# SpinASM.net
KiCad netlist of a schematic drawn in Altium Designer
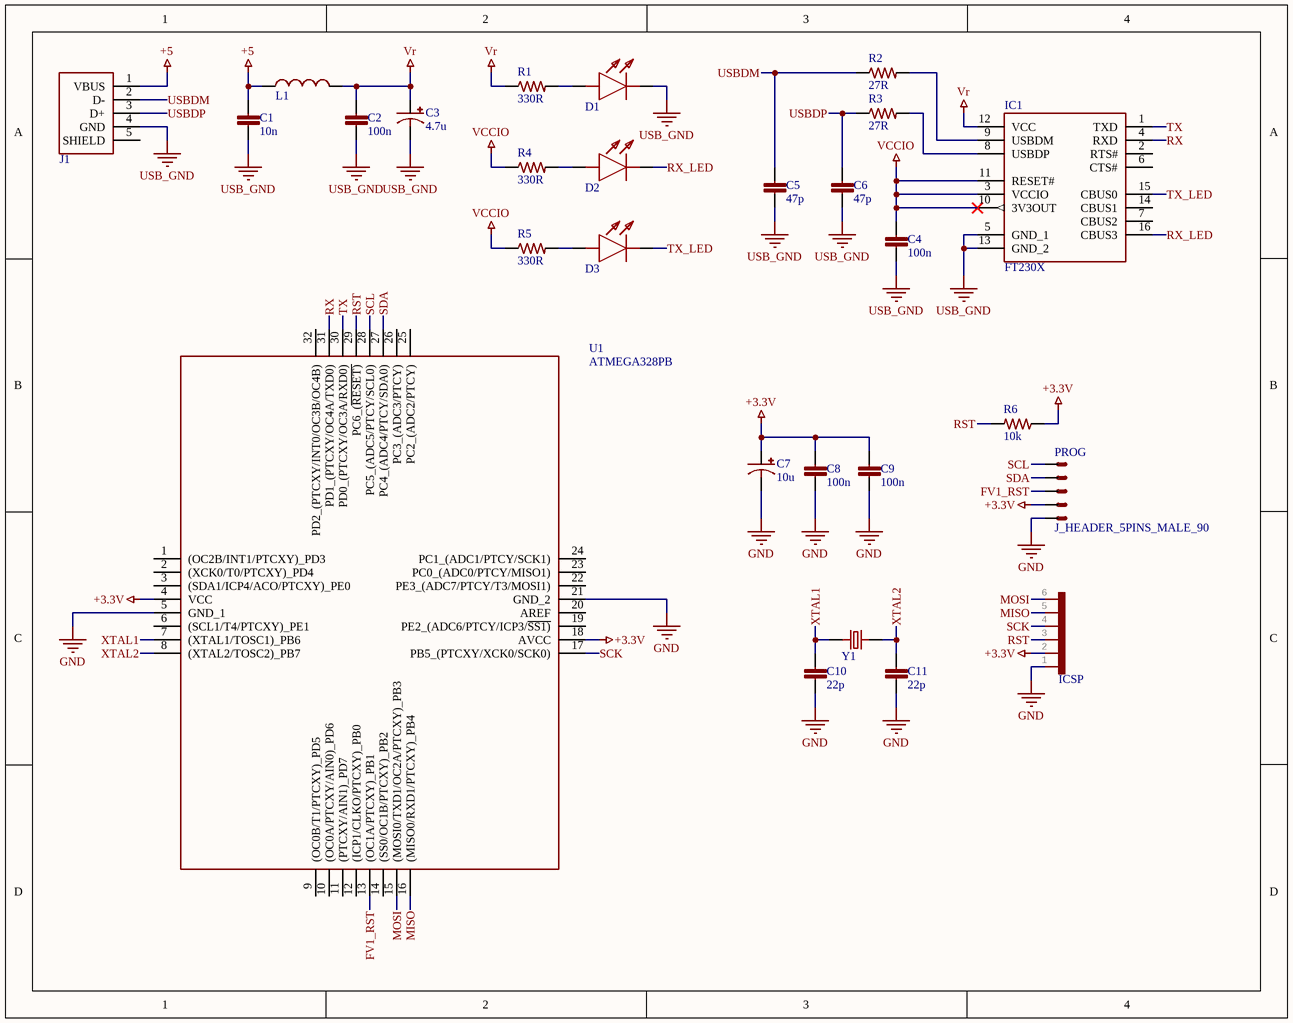
[diagram p0: SpinASM.SchDoc]

(export (version "E")
  (design (tool "Eeschema 10.0.6"))
  (components
    (comp (ref "C1")
      (value "10n")
      (footprint "CHIP_0603")
      (description "CAP CER 10NF 50V X7R 0603")
      (fields
        (field (name "MANUFACTURER") "Multicomp")
        (field (name "MANUFACTURER PART NUMBER") "MC0603B103K500CT")
      )
      (libsource (lib "Pedals SMD") (part "MC0603B103K500CT"))
    )
    (comp (ref "C2")
      (value "100n")
      (footprint "CHIP_0603")
      (description "CAP CER 100NF 50V X7R 0603")
      (fields
        (field (name "MANUFACTURER") "Multicomp")
        (field (name "MANUFACTURER PART NUMBER") "MC0603B104K500CT")
      )
      (libsource (lib "Pedals SMD") (part "MC0603B104K500CT"))
    )
    (comp (ref "C3")
      (value "4.7u")
      (footprint "TAN_1206")
      (description "CAP TANT 4.7UF 10V")
      (fields
        (field (name "MANUFACTURER") "KEMET")
        (field (name "MANUFACTURER PART NUMBER") "T491A475K010AT")
      )
      (libsource (lib "Pedals SMD") (part "T491A475K010AT"))
    )
    (comp (ref "C4")
      (value "100n")
      (footprint "CHIP_0603")
      (description "CAP CER 100NF 50V X7R 0603")
      (fields
        (field (name "MANUFACTURER") "Multicomp")
        (field (name "MANUFACTURER PART NUMBER") "MC0603B104K500CT")
      )
      (libsource (lib "Pedals SMD") (part "MC0603B104K500CT"))
    )
    (comp (ref "C5")
      (value "47p")
      (footprint "CHIP_0603")
      (description "CAP CER 47PF 50V C0G/NP0 0603")
      (fields
        (field (name "MANUFACTURER") "Multicomp")
        (field (name "MANUFACTURER PART NUMBER") "MC0603N470J500CT")
      )
      (libsource (lib "Pedals SMD") (part "MC0603N470J500CT"))
    )
    (comp (ref "C6")
      (value "47p")
      (footprint "CHIP_0603")
      (description "CAP CER 47PF 50V C0G/NP0 0603")
      (fields
        (field (name "MANUFACTURER") "Multicomp")
        (field (name "MANUFACTURER PART NUMBER") "MC0603N470J500CT")
      )
      (libsource (lib "Pedals SMD") (part "MC0603N470J500CT"))
    )
    (comp (ref "C7")
      (value "10u")
      (footprint "TAN_1206")
      (description "CAP TANT 10UF 16V")
      (fields
        (field (name "MANUFACTURER") "KEMET")
        (field (name "MANUFACTURER PART NUMBER") "T491A106K016AT")
      )
      (libsource (lib "Pedals SMD") (part "T491A106K016AT"))
    )
    (comp (ref "C8")
      (value "100n")
      (footprint "CHIP_0603")
      (description "CAP CER 100NF 50V X7R 0603")
      (fields
        (field (name "MANUFACTURER") "Multicomp")
        (field (name "MANUFACTURER PART NUMBER") "MC0603B104K500CT")
      )
      (libsource (lib "Pedals SMD") (part "MC0603B104K500CT"))
    )
    (comp (ref "C9")
      (value "100n")
      (footprint "CHIP_0603")
      (description "CAP CER 100NF 50V X7R 0603")
      (fields
        (field (name "MANUFACTURER") "Multicomp")
        (field (name "MANUFACTURER PART NUMBER") "MC0603B104K500CT")
      )
      (libsource (lib "Pedals SMD") (part "MC0603B104K500CT"))
    )
    (comp (ref "C10")
      (value "22p")
      (footprint "CHIP_0603")
      (description "CAP CER 22PF 50V C0G/NP0 0603")
      (fields
        (field (name "MANUFACTURER") "Multicomp")
        (field (name "MANUFACTURER PART NUMBER") "MC0603N220J500CT")
      )
      (libsource (lib "Pedals SMD") (part "MC0603N220J500CT"))
    )
    (comp (ref "C11")
      (value "22p")
      (footprint "CHIP_0603")
      (description "CAP CER 22PF 50V C0G/NP0 0603")
      (fields
        (field (name "MANUFACTURER") "Multicomp")
        (field (name "MANUFACTURER PART NUMBER") "MC0603N220J500CT")
      )
      (libsource (lib "Pedals SMD") (part "MC0603N220J500CT"))
    )
    (comp (ref "D1")
      (value "MP001249")
      (footprint "LED_0603")
      (description "LED RED CMS 603 20 mA 2.5 V 629 nm")
      (fields (field (name "MANUFACTURER") "Multicomp"))
      (libsource (lib "Pedals SMD") (part "MP001249"))
    )
    (comp (ref "D2")
      (value "MP001249")
      (footprint "LED_0603")
      (description "LED RED CMS 603 20 mA 2.5 V 629 nm")
      (fields (field (name "MANUFACTURER") "Multicomp"))
      (libsource (lib "Pedals SMD") (part "MP001249"))
    )
    (comp (ref "D3")
      (value "MP001249")
      (footprint "LED_0603")
      (description "LED RED CMS 603 20 mA 2.5 V 629 nm")
      (fields (field (name "MANUFACTURER") "Multicomp"))
      (libsource (lib "Pedals SMD") (part "MP001249"))
    )
    (comp (ref "IC1")
      (value "FT230X")
      (footprint "TSSOP-16")
      (description "USB-to-UART 1-CH 512byte FIFO 5V 16-Pin SSOP T/R")
      (fields (field (name "MANUFACTURER") "FTDI") (field (name "MANUFACTURER PART NUMBER") "FT230XS-R"))
      (libsource (lib "Pedals SMD") (part "FT230XS-R"))
    )
    (comp (ref "ICSP")
      (value "ICSP")
      (footprint "AVRISP_POGO")
      (libsource (lib "Pedals SMD") (part "AVRISP_POGO"))
    )
    (comp (ref "J1")
      (value "USB_MALE")
      (footprint "USB_MALE")
      (description "USB Connectors USB A PLUG SMT STR S SHELL LEG 3.8mm L/F")
      (fields (field (name "MANUFACTURER") "Molex") (field (name "MANUFACTURER PART NUMBER") "48037-2200"))
      (libsource (lib "Pedals SMD") (part "48037-2200"))
    )
    (comp (ref "L1")
      (value "BLM18AG331SN1D")
      (footprint "INDC1608X10")
      (description "MURATA         BLM18AG331SN1D            FERRITE BEAD, 0.3OHM, 500MA, 0603")
      (fields (field (name "MANUFACTURER") "Murata") (field (name "TOLERANCE") "25%"))
      (libsource (lib "Pedals SMD") (part "BLM18AG331SN1D"))
    )
    (comp (ref "PROG")
      (value "J_HEADER_5PINS_MALE_90")
      (footprint "HEADER_5PINS_MALE_90")
      (libsource (lib "Pedals") (part "J_HEADER_5PINS_MALE_90"))
    )
    (comp (ref "R1")
      (value "330R")
      (footprint "CHIP_R_0603")
      (description "RES SMD 330R OHM 1% 1/10W 0603")
      (fields
        (field (name "MANUFACTURER") "Vishay")
        (field (name "MANUFACTURER PART NUMBER") "CRCW0603330RFKEA")
      )
      (libsource (lib "Pedals SMD") (part "CRCW0603330RFKEA"))
    )
    (comp (ref "R2")
      (value "27R")
      (footprint "CHIP_R_0603")
      (description "RES SMD 27 OHM 1% 1/10W 0603")
      (fields
        (field (name "MANUFACTURER") "Vishay")
        (field (name "MANUFACTURER PART NUMBER") "CRCW060327R0FKEA")
      )
      (libsource (lib "Pedals SMD") (part "CRCW060327R0FKEA"))
    )
    (comp (ref "R3")
      (value "27R")
      (footprint "CHIP_R_0603")
      (description "RES SMD 27 OHM 1% 1/10W 0603")
      (fields
        (field (name "MANUFACTURER") "Vishay")
        (field (name "MANUFACTURER PART NUMBER") "CRCW060327R0FKEA")
      )
      (libsource (lib "Pedals SMD") (part "CRCW060327R0FKEA"))
    )
    (comp (ref "R4")
      (value "330R")
      (footprint "CHIP_R_0603")
      (description "RES SMD 330R OHM 1% 1/10W 0603")
      (fields
        (field (name "MANUFACTURER") "Vishay")
        (field (name "MANUFACTURER PART NUMBER") "CRCW0603330RFKEA")
      )
      (libsource (lib "Pedals SMD") (part "CRCW0603330RFKEA"))
    )
    (comp (ref "R5")
      (value "330R")
      (footprint "CHIP_R_0603")
      (description "RES SMD 330R OHM 1% 1/10W 0603")
      (fields
        (field (name "MANUFACTURER") "Vishay")
        (field (name "MANUFACTURER PART NUMBER") "CRCW0603330RFKEA")
      )
      (libsource (lib "Pedals SMD") (part "CRCW0603330RFKEA"))
    )
    (comp (ref "R6")
      (value "10k")
      (footprint "CHIP_R_0603")
      (description "RES SMD 10K OHM 1% 1/10W 0603")
      (fields
        (field (name "MANUFACTURER") "Vishay")
        (field (name "MANUFACTURER PART NUMBER") "CRCW060310K0FKEA")
      )
      (libsource (lib "Pedals SMD") (part "CRCW060310K0FKEA"))
    )
    (comp (ref "U1")
      (value "ATMEGA328PB")
      (footprint "TQFP32")
      (description "IC MCU 8BIT 32KB FLASH 32TQFP")
      (fields
        (field (name "MANUFACTURER") "Microchip")
        (field (name "MANUFACTURER PART NUMBER") "ATMEGA328PB-AU")
      )
      (libsource (lib "Pedals SMD") (part "ATMEGA328PB-AU"))
    )
    (comp (ref "Y1")
      (value "ABM10")
      (footprint "ABM10-167")
      (description "CRYSTAL 12 MHz SMD 28 pF 10 ppm")
      (fields
        (field (name "MANUFACTURER") "Abracon")
        (field (name "MANUFACTURER PART NUMBER") "ABM10-166-12.000MHZ-T3")
      )
      (libsource (lib "Pedals SMD") (part "ABM10-166-12.000MHZ-T3"))
    )
  )
  (nets
    (net (code "1") (name "+3.3V") (class "Default")
      (node (ref "C7") (pin "+") (pinfunction "+_+") (pintype "passive"))
      (node (ref "C8") (pin "1") (pinfunction "1_1") (pintype "passive"))
      (node (ref "C9") (pin "1") (pinfunction "1_1") (pintype "passive"))
      (node (ref "ICSP") (pin "2") (pinfunction "MOSI_2") (pintype "power_in"))
      (node (ref "PROG") (pin "2") (pinfunction "S_2") (pintype "passive"))
      (node (ref "R6") (pin "1") (pinfunction "1_1") (pintype "passive"))
      (node (ref "U1") (pin "18") (pinfunction "AVCC_18") (pintype "passive"))
      (node (ref "U1") (pin "4") (pinfunction "VCC_4") (pintype "passive"))
    )
    (net (code "2") (name "+5") (class "Default")
      (node (ref "C1") (pin "1") (pinfunction "1_1") (pintype "passive"))
      (node (ref "J1") (pin "1") (pinfunction "VBUS_1") (pintype "passive"))
      (node (ref "L1") (pin "2") (pinfunction "2_2") (pintype "passive"))
    )
    (net (code "3") (name "/FV1_RST") (class "Default")
      (node (ref "PROG") (pin "3") (pinfunction "S_3") (pintype "passive"))
      (node (ref "U1") (pin "13") (pinfunction "(OC1A/PTCXY)_PB1_13") (pintype "passive"))
    )
    (net (code "4") (name "/MISO") (class "Default")
      (node (ref "ICSP") (pin "5") (pinfunction "GND_5") (pintype "power_in"))
      (node (ref "U1") (pin "16") (pinfunction "(MISO0/RXD1/PTCXY)_PB4_16") (pintype "passive"))
    )
    (net (code "5") (name "/MOSI") (class "Default")
      (node (ref "ICSP") (pin "6") (pinfunction "VCC_6") (pintype "power_in"))
      (node (ref "U1") (pin "15") (pinfunction "(MOSI0/TXD1/OC2A/PTCXY)_PB3_15") (pintype "passive"))
    )
    (net (code "6") (name "/RST") (class "Default")
      (node (ref "ICSP") (pin "3") (pinfunction "MISO_3") (pintype "power_in"))
      (node (ref "R6") (pin "2") (pinfunction "2_2") (pintype "passive"))
      (node (ref "U1") (pin "29") (pinfunction "PC6_(~{RESET)}_29") (pintype "passive"))
    )
    (net (code "7") (name "/RX") (class "Default")
      (node (ref "IC1") (pin "4") (pinfunction "RXD_4") (pintype "passive"))
      (node (ref "U1") (pin "31") (pinfunction "PD1_(PTCXY/OC4A/TXD0)_31") (pintype "passive"))
    )
    (net (code "8") (name "/RX_LED") (class "Default")
      (node (ref "D2") (pin "1") (pinfunction "K_1") (pintype "passive"))
      (node (ref "IC1") (pin "16") (pinfunction "CBUS3_16") (pintype "passive"))
    )
    (net (code "9") (name "/SCK") (class "Default")
      (node (ref "ICSP") (pin "4") (pinfunction "SCK_4") (pintype "power_in"))
      (node (ref "U1") (pin "17") (pinfunction "PB5_(PTCXY/XCK0/SCK0)_17") (pintype "passive"))
    )
    (net (code "10") (name "/SCL") (class "Default")
      (node (ref "PROG") (pin "5") (pinfunction "S_5") (pintype "passive"))
      (node (ref "U1") (pin "28") (pinfunction "PC5_(ADC5/PTCY/SCL0)_28") (pintype "passive"))
    )
    (net (code "11") (name "/SDA") (class "Default")
      (node (ref "PROG") (pin "4") (pinfunction "S_4") (pintype "passive"))
      (node (ref "U1") (pin "27") (pinfunction "PC4_(ADC4/PTCY/SDA0)_27") (pintype "passive"))
    )
    (net (code "12") (name "/TX") (class "Default")
      (node (ref "IC1") (pin "1") (pinfunction "TXD_1") (pintype "passive"))
      (node (ref "U1") (pin "30") (pinfunction "PD0_(PTCXY/OC3A/RXD0)_30") (pintype "passive"))
    )
    (net (code "13") (name "/TX_LED") (class "Default")
      (node (ref "D3") (pin "1") (pinfunction "K_1") (pintype "passive"))
      (node (ref "IC1") (pin "15") (pinfunction "CBUS0_15") (pintype "passive"))
    )
    (net (code "14") (name "/USBDM") (class "Default")
      (node (ref "C5") (pin "1") (pinfunction "1_1") (pintype "passive"))
      (node (ref "J1") (pin "2") (pinfunction "D-_2") (pintype "passive"))
      (node (ref "R2") (pin "1") (pinfunction "1_1") (pintype "passive"))
    )
    (net (code "15") (name "/USBDP") (class "Default")
      (node (ref "C6") (pin "1") (pinfunction "1_1") (pintype "passive"))
      (node (ref "J1") (pin "3") (pinfunction "D+_3") (pintype "passive"))
      (node (ref "R3") (pin "1") (pinfunction "1_1") (pintype "passive"))
    )
    (net (code "16") (name "/XTAL1") (class "Default")
      (node (ref "C10") (pin "1") (pinfunction "1_1") (pintype "passive"))
      (node (ref "U1") (pin "7") (pinfunction "(XTAL1/TOSC1)_PB6_7") (pintype "passive"))
      (node (ref "Y1") (pin "1") (pinfunction "1_1") (pintype "passive"))
    )
    (net (code "17") (name "/XTAL2") (class "Default")
      (node (ref "C11") (pin "1") (pinfunction "1_1") (pintype "passive"))
      (node (ref "U1") (pin "8") (pinfunction "(XTAL2/TOSC2)_PB7_8") (pintype "passive"))
      (node (ref "Y1") (pin "2") (pinfunction "2_2") (pintype "passive"))
    )
    (net (code "18") (name "GND") (class "Default")
      (node (ref "C10") (pin "2") (pinfunction "2_2") (pintype "passive"))
      (node (ref "C11") (pin "2") (pinfunction "2_2") (pintype "passive"))
      (node (ref "C7") (pin "-") (pinfunction "-_-") (pintype "passive"))
      (node (ref "C8") (pin "2") (pinfunction "2_2") (pintype "passive"))
      (node (ref "C9") (pin "2") (pinfunction "2_2") (pintype "passive"))
      (node (ref "ICSP") (pin "1") (pinfunction "RST_1") (pintype "power_in"))
      (node (ref "PROG") (pin "1") (pinfunction "S_1") (pintype "passive"))
      (node (ref "U1") (pin "21") (pinfunction "GND_2_21") (pintype "passive"))
      (node (ref "U1") (pin "5") (pinfunction "GND_1_5") (pintype "passive"))
    )
    (net (code "19") (name "Net-(D1-A)") (class "Default")
      (node (ref "D1") (pin "2") (pinfunction "A_2") (pintype "passive"))
      (node (ref "R1") (pin "2") (pinfunction "2_2") (pintype "passive"))
    )
    (net (code "20") (name "Net-(D2-A)") (class "Default")
      (node (ref "D2") (pin "2") (pinfunction "A_2") (pintype "passive"))
      (node (ref "R4") (pin "2") (pinfunction "2_2") (pintype "passive"))
    )
    (net (code "21") (name "Net-(D3-A)") (class "Default")
      (node (ref "D3") (pin "2") (pinfunction "A_2") (pintype "passive"))
      (node (ref "R5") (pin "2") (pinfunction "2_2") (pintype "passive"))
    )
    (net (code "22") (name "Net-(IC1-USBDM)") (class "Default")
      (node (ref "IC1") (pin "9") (pinfunction "USBDM_9") (pintype "passive"))
      (node (ref "R2") (pin "2") (pinfunction "2_2") (pintype "passive"))
    )
    (net (code "23") (name "Net-(IC1-USBDP)") (class "Default")
      (node (ref "IC1") (pin "8") (pinfunction "USBDP_8") (pintype "passive"))
      (node (ref "R3") (pin "2") (pinfunction "2_2") (pintype "passive"))
    )
    (net (code "24") (name "USB_GND") (class "Default")
      (node (ref "C1") (pin "2") (pinfunction "2_2") (pintype "passive"))
      (node (ref "C2") (pin "2") (pinfunction "2_2") (pintype "passive"))
      (node (ref "C3") (pin "-") (pinfunction "-_-") (pintype "passive"))
      (node (ref "C4") (pin "2") (pinfunction "2_2") (pintype "passive"))
      (node (ref "C5") (pin "2") (pinfunction "2_2") (pintype "passive"))
      (node (ref "C6") (pin "2") (pinfunction "2_2") (pintype "passive"))
      (node (ref "D1") (pin "1") (pinfunction "K_1") (pintype "passive"))
      (node (ref "IC1") (pin "13") (pinfunction "GND_2_13") (pintype "power_in"))
      (node (ref "IC1") (pin "5") (pinfunction "GND_1_5") (pintype "power_in"))
      (node (ref "J1") (pin "4") (pinfunction "GND_4") (pintype "passive"))
    )
    (net (code "25") (name "VCCIO") (class "Default")
      (node (ref "C4") (pin "1") (pinfunction "1_1") (pintype "passive"))
      (node (ref "IC1") (pin "10") (pinfunction "3V3OUT_10") (pintype "output"))
      (node (ref "IC1") (pin "11") (pinfunction "RESET#_11") (pintype "passive"))
      (node (ref "IC1") (pin "3") (pinfunction "VCCIO_3") (pintype "power_in"))
      (node (ref "R4") (pin "1") (pinfunction "1_1") (pintype "passive"))
      (node (ref "R5") (pin "1") (pinfunction "1_1") (pintype "passive"))
    )
    (net (code "26") (name "Vr") (class "Default")
      (node (ref "C2") (pin "1") (pinfunction "1_1") (pintype "passive"))
      (node (ref "C3") (pin "+") (pinfunction "+_+") (pintype "passive"))
      (node (ref "IC1") (pin "12") (pinfunction "VCC_12") (pintype "power_in"))
      (node (ref "L1") (pin "1") (pinfunction "1_1") (pintype "passive"))
      (node (ref "R1") (pin "1") (pinfunction "1_1") (pintype "passive"))
    )
    (net (code "27") (name "unconnected-(IC1-CBUS1-Pad14)") (class "Default")
      (node (ref "IC1") (pin "14") (pinfunction "CBUS1_14") (pintype "passive"))
    )
    (net (code "28") (name "unconnected-(IC1-CBUS2-Pad7)") (class "Default")
      (node (ref "IC1") (pin "7") (pinfunction "CBUS2_7") (pintype "passive"))
    )
    (net (code "29") (name "unconnected-(IC1-CTS#-Pad6)") (class "Default")
      (node (ref "IC1") (pin "6") (pinfunction "CTS#_6") (pintype "passive"))
    )
    (net (code "30") (name "unconnected-(IC1-RTS#-Pad2)") (class "Default")
      (node (ref "IC1") (pin "2") (pinfunction "RTS#_2") (pintype "passive"))
    )
    (net (code "31") (name "unconnected-(J1-SHIELD-Pad5)") (class "Default")
      (node (ref "J1") (pin "5") (pinfunction "SHIELD_5") (pintype "passive"))
    )
    (net (code "32") (name "unconnected-(U1-(ICP1{slash}CLKO{slash}PTCXY)_PB0-Pad12)") (class "Default")
      (node (ref "U1") (pin "12") (pinfunction "(ICP1/CLKO/PTCXY)_PB0_12") (pintype "passive"))
    )
    (net (code "33") (name "unconnected-(U1-(OC0A{slash}PTCXY{slash}AIN0)_PD6-Pad10)") (class "Default")
      (node (ref "U1") (pin "10") (pinfunction "(OC0A/PTCXY/AIN0)_PD6_10") (pintype "passive"))
    )
    (net (code "34") (name "unconnected-(U1-(OC0B{slash}T1{slash}PTCXY)_PD5-Pad9)") (class "Default")
      (node (ref "U1") (pin "9") (pinfunction "(OC0B/T1/PTCXY)_PD5_9") (pintype "passive"))
    )
    (net (code "35") (name "unconnected-(U1-(OC2B{slash}INT1{slash}PTCXY)_PD3-Pad1)") (class "Default")
      (node (ref "U1") (pin "1") (pinfunction "(OC2B/INT1/PTCXY)_PD3_1") (pintype "passive"))
    )
    (net (code "36") (name "unconnected-(U1-(PTCXY{slash}AIN1)_PD7-Pad11)") (class "Default")
      (node (ref "U1") (pin "11") (pinfunction "(PTCXY/AIN1)_PD7_11") (pintype "passive"))
    )
    (net (code "37") (name "unconnected-(U1-(SCL1{slash}T4{slash}PTCXY)_PE1-Pad6)") (class "Default")
      (node (ref "U1") (pin "6") (pinfunction "(SCL1/T4/PTCXY)_PE1_6") (pintype "passive"))
    )
    (net (code "38") (name "unconnected-(U1-(SDA1{slash}ICP4{slash}ACO{slash}PTCXY)_PE0-Pad3)") (class "Default")
      (node (ref "U1") (pin "3") (pinfunction "(SDA1/ICP4/ACO/PTCXY)_PE0_3") (pintype "passive"))
    )
    (net (code "39") (name "unconnected-(U1-(SS0{slash}OC1B{slash}PTCXY)_PB2-Pad14)") (class "Default")
      (node (ref "U1") (pin "14") (pinfunction "(SS0/OC1B/PTCXY)_PB2_14") (pintype "passive"))
    )
    (net (code "40") (name "unconnected-(U1-(XCK0{slash}T0{slash}PTCXY)_PD4-Pad2)") (class "Default")
      (node (ref "U1") (pin "2") (pinfunction "(XCK0/T0/PTCXY)_PD4_2") (pintype "passive"))
    )
    (net (code "41") (name "unconnected-(U1-AREF-Pad20)") (class "Default")
      (node (ref "U1") (pin "20") (pinfunction "AREF_20") (pintype "passive"))
    )
    (net (code "42") (name "unconnected-(U1-PC0_(ADC0{slash}PTCY{slash}MISO1)-Pad23)") (class "Default")
      (node (ref "U1") (pin "23") (pinfunction "PC0_(ADC0/PTCY/MISO1)_23") (pintype "passive"))
    )
    (net (code "43") (name "unconnected-(U1-PC1_(ADC1{slash}PTCY{slash}SCK1)-Pad24)") (class "Default")
      (node (ref "U1") (pin "24") (pinfunction "PC1_(ADC1/PTCY/SCK1)_24") (pintype "passive"))
    )
    (net (code "44") (name "unconnected-(U1-PC2_(ADC2{slash}PTCY)-Pad25)") (class "Default")
      (node (ref "U1") (pin "25") (pinfunction "PC2_(ADC2/PTCY)_25") (pintype "passive"))
    )
    (net (code "45") (name "unconnected-(U1-PC3_(ADC3{slash}PTCY)-Pad26)") (class "Default")
      (node (ref "U1") (pin "26") (pinfunction "PC3_(ADC3/PTCY)_26") (pintype "passive"))
    )
    (net (code "46") (name "unconnected-(U1-PD2_(PTCXY{slash}INT0{slash}OC3B{slash}OC4B)-Pad32)") (class "Default")
      (node (ref "U1") (pin "32") (pinfunction "PD2_(PTCXY/INT0/OC3B/OC4B)_32") (pintype "passive"))
    )
    (net (code "47") (name "unconnected-(U1-PE2_(ADC6{slash}PTCY{slash}ICP3{slash}~{SS1)}-Pad19)") (class "Default")
      (node (ref "U1") (pin "19") (pinfunction "PE2_(ADC6/PTCY/ICP3/~{SS1)}_19") (pintype "passive"))
    )
    (net (code "48") (name "unconnected-(U1-PE3_(ADC7{slash}PTCY{slash}T3{slash}MOSI1)-Pad22)") (class "Default")
      (node (ref "U1") (pin "22") (pinfunction "PE3_(ADC7/PTCY/T3/MOSI1)_22") (pintype "passive"))
    )
  )
)
